# OLED_Shield_RV_2.net
KiCad netlist of a schematic drawn in EAGLE
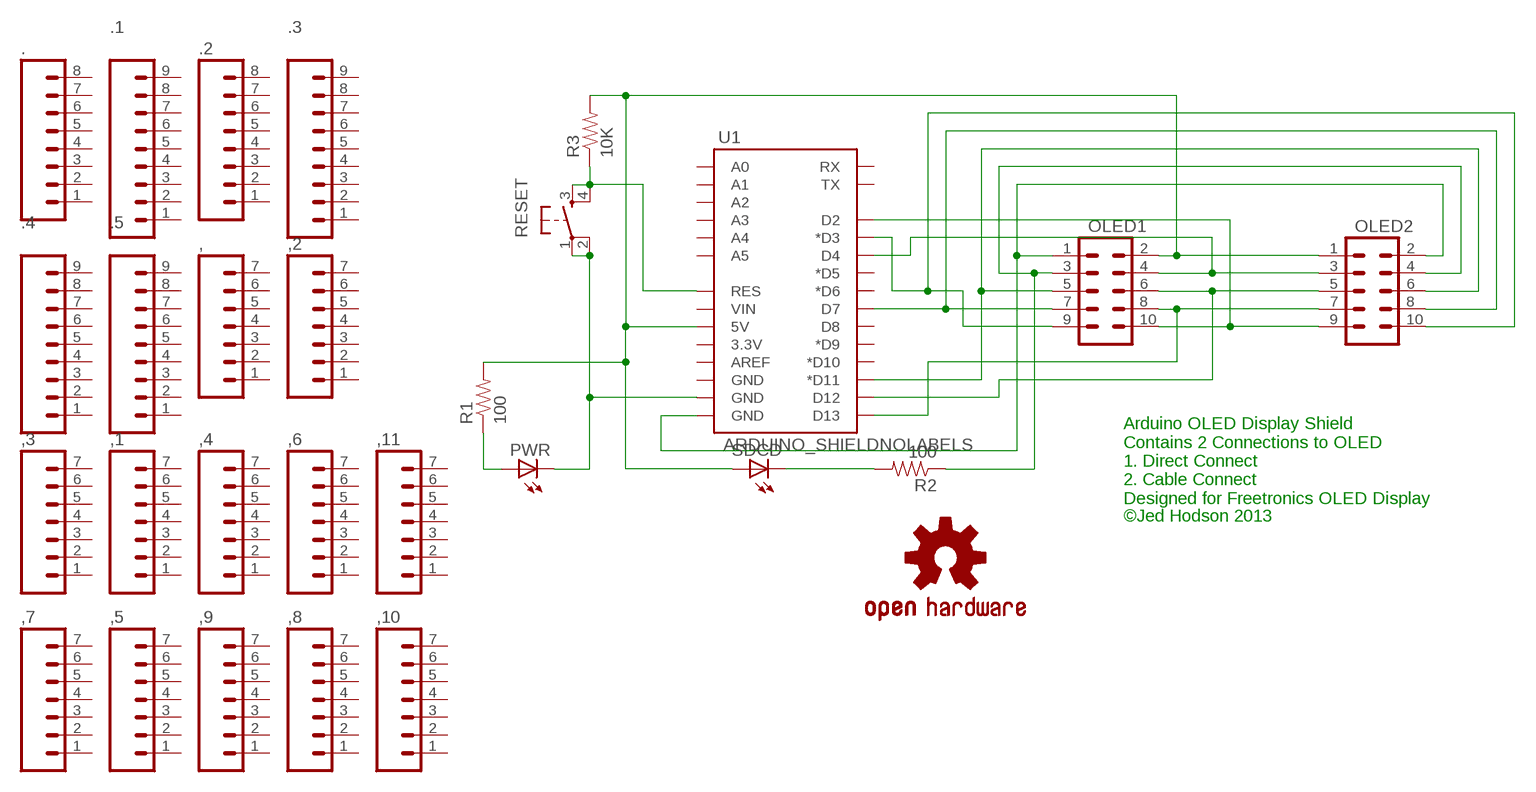
[diagram p0: schematic, sheet 1]

(export (version "E")
  (design (tool "Eeschema 10.0.6"))
  (components
    (comp (ref ",")
      (value "M07")
      (footprint "eagle-import:1X07")
      (libsource (lib "eagle-import") (part "M07"))
    )
    (comp (ref ",1")
      (value "M07")
      (footprint "eagle-import:1X07")
      (libsource (lib "eagle-import") (part "M07"))
    )
    (comp (ref ",2")
      (value "M07")
      (footprint "eagle-import:1X07")
      (libsource (lib "eagle-import") (part "M07"))
    )
    (comp (ref ",3")
      (value "M07")
      (footprint "eagle-import:1X07")
      (libsource (lib "eagle-import") (part "M07"))
    )
    (comp (ref ",4")
      (value "M07")
      (footprint "eagle-import:1X07")
      (libsource (lib "eagle-import") (part "M07"))
    )
    (comp (ref ",5")
      (value "M07")
      (footprint "eagle-import:1X07")
      (libsource (lib "eagle-import") (part "M07"))
    )
    (comp (ref ",6")
      (value "M07")
      (footprint "eagle-import:1X07")
      (libsource (lib "eagle-import") (part "M07"))
    )
    (comp (ref ",7")
      (value "M07")
      (footprint "eagle-import:1X07")
      (libsource (lib "eagle-import") (part "M07"))
    )
    (comp (ref ",8")
      (value "M07")
      (footprint "eagle-import:1X07")
      (libsource (lib "eagle-import") (part "M07"))
    )
    (comp (ref ",9")
      (value "M07")
      (footprint "eagle-import:1X07")
      (libsource (lib "eagle-import") (part "M07"))
    )
    (comp (ref ",10")
      (value "M07")
      (footprint "eagle-import:1X07")
      (libsource (lib "eagle-import") (part "M07"))
    )
    (comp (ref ",11")
      (value "M07")
      (footprint "eagle-import:1X07")
      (libsource (lib "eagle-import") (part "M07"))
    )
    (comp (ref ".")
      (value "M081X08")
      (footprint "eagle-import:1X08")
      (libsource (lib "eagle-import") (part "M081X08"))
    )
    (comp (ref ".1")
      (value "M09")
      (footprint "eagle-import:1X09")
      (libsource (lib "eagle-import") (part "M09"))
    )
    (comp (ref ".2")
      (value "M081X08")
      (footprint "eagle-import:1X08")
      (libsource (lib "eagle-import") (part "M081X08"))
    )
    (comp (ref ".3")
      (value "M09")
      (footprint "eagle-import:1X09")
      (libsource (lib "eagle-import") (part "M09"))
    )
    (comp (ref ".4")
      (value "M09")
      (footprint "eagle-import:1X09")
      (libsource (lib "eagle-import") (part "M09"))
    )
    (comp (ref ".5")
      (value "M09")
      (footprint "eagle-import:1X09")
      (libsource (lib "eagle-import") (part "M09"))
    )
    (comp (ref "LOGO1")
      (value "OSHW-LOGOL")
      (footprint "eagle-import:OSHW-LOGO-L")
      (libsource (lib "eagle-import") (part "OSHW-LOGOL"))
    )
    (comp (ref "OLED1")
      (value "M05X2PTH")
      (footprint "eagle-import:AVR_ICSP")
      (libsource (lib "eagle-import") (part "M05X2PTH"))
    )
    (comp (ref "OLED2")
      (value "M05X2PTH")
      (footprint "eagle-import:AVR_ICSP")
      (libsource (lib "eagle-import") (part "M05X2PTH"))
    )
    (comp (ref "PWR")
      (value "LED5MM")
      (footprint "eagle-import:LED5MM")
      (libsource (lib "eagle-import") (part "LED5MM"))
    )
    (comp (ref "R1")
      (value "100")
      (footprint "eagle-import:AXIAL-0.4")
      (libsource (lib "eagle-import") (part "RESISTORPTH-1/4W"))
    )
    (comp (ref "R2")
      (value "100")
      (footprint "eagle-import:AXIAL-0.4")
      (libsource (lib "eagle-import") (part "RESISTORPTH-1/4W"))
    )
    (comp (ref "R3")
      (value "10K")
      (footprint "eagle-import:AXIAL-0.4")
      (libsource (lib "eagle-import") (part "RESISTORPTH-1/4W"))
    )
    (comp (ref "RESET")
      (value "TAC_SWITCHPTH")
      (footprint "eagle-import:TACTILE-PTH")
      (libsource (lib "eagle-import") (part "TAC_SWITCHPTH"))
    )
    (comp (ref "SDCD")
      (value "LED5MM")
      (footprint "eagle-import:LED5MM")
      (libsource (lib "eagle-import") (part "LED5MM"))
    )
    (comp (ref "U1")
      (value "ARDUINO_SHIELDNOLABELS")
      (footprint "eagle-import:DUEMILANOVE_SHIELD_NOLABELS")
      (libsource (lib "eagle-import") (part "ARDUINO_SHIELDNOLABELS"))
    )
  )
  (nets
    (net (code "1") (name "Net-(OLED1-Pad1)") (class "Default")
      (node (ref "OLED1") (pin "1") (pinfunction "1_1") (pintype "passive"))
      (node (ref "OLED2") (pin "2") (pinfunction "2_2") (pintype "passive"))
      (node (ref "U1") (pin "GND@0") (pinfunction "GND_GND@0") (pintype "bidirectional"))
    )
    (net (code "2") (name "Net-(OLED1-Pad4)") (class "Default")
      (node (ref "OLED1") (pin "4") (pinfunction "4_4") (pintype "passive"))
      (node (ref "OLED2") (pin "3") (pinfunction "3_3") (pintype "passive"))
      (node (ref "U1") (pin "D4") (pinfunction "D4_D4") (pintype "bidirectional"))
    )
    (net (code "3") (name "Net-(OLED1-Pad6)") (class "Default")
      (node (ref "OLED1") (pin "6") (pinfunction "6_6") (pintype "passive"))
      (node (ref "OLED2") (pin "5") (pinfunction "5_5") (pintype "passive"))
      (node (ref "U1") (pin "D12") (pinfunction "D12_D12") (pintype "bidirectional"))
    )
    (net (code "4") (name "Net-(OLED1-Pad7)") (class "Default")
      (node (ref "OLED1") (pin "7") (pinfunction "7_7") (pintype "passive"))
      (node (ref "OLED2") (pin "8") (pinfunction "8_8") (pintype "passive"))
      (node (ref "U1") (pin "D7") (pinfunction "D7_D7") (pintype "bidirectional"))
    )
    (net (code "5") (name "Net-(OLED1-Pad8)") (class "Default")
      (node (ref "OLED1") (pin "8") (pinfunction "8_8") (pintype "passive"))
      (node (ref "OLED2") (pin "7") (pinfunction "7_7") (pintype "passive"))
      (node (ref "U1") (pin "D13") (pinfunction "D13_D13") (pintype "bidirectional"))
    )
    (net (code "6") (name "Net-(OLED1-Pad10)") (class "Default")
      (node (ref "OLED1") (pin "10") (pinfunction "10_10") (pintype "passive"))
      (node (ref "OLED2") (pin "9") (pinfunction "9_9") (pintype "passive"))
      (node (ref "U1") (pin "D2") (pinfunction "D2_D2") (pintype "bidirectional"))
    )
    (net (code "7") (name "Net-(PWR-C)") (class "Default")
      (node (ref "PWR") (pin "K") (pinfunction "C_K") (pintype "passive"))
      (node (ref "RESET") (pin "1") (pinfunction "1_1") (pintype "passive"))
      (node (ref "RESET") (pin "2") (pinfunction "2_2") (pintype "passive"))
      (node (ref "U1") (pin "GND@1") (pinfunction "GND_GND@1") (pintype "bidirectional"))
    )
    (net (code "8") (name "Net-(R1-1)") (class "Default")
      (node (ref "PWR") (pin "A") (pinfunction "A_A") (pintype "passive"))
      (node (ref "R1") (pin "P$1") (pinfunction "1_P$1") (pintype "passive"))
    )
    (net (code "9") (name "Net-(R1-2)") (class "Default")
      (node (ref "OLED1") (pin "2") (pinfunction "2_2") (pintype "passive"))
      (node (ref "OLED2") (pin "1") (pinfunction "1_1") (pintype "passive"))
      (node (ref "R1") (pin "P$2") (pinfunction "2_P$2") (pintype "passive"))
      (node (ref "R3") (pin "P$2") (pinfunction "2_P$2") (pintype "passive"))
      (node (ref "SDCD") (pin "A") (pinfunction "A_A") (pintype "passive"))
      (node (ref "U1") (pin "5V") (pinfunction "5V_5V") (pintype "bidirectional"))
    )
    (net (code "10") (name "Net-(R2-1)") (class "Default")
      (node (ref "OLED1") (pin "3") (pinfunction "3_3") (pintype "passive"))
      (node (ref "OLED2") (pin "4") (pinfunction "4_4") (pintype "passive"))
      (node (ref "R2") (pin "P$1") (pinfunction "1_P$1") (pintype "passive"))
    )
    (net (code "11") (name "Net-(R2-2)") (class "Default")
      (node (ref "R2") (pin "P$2") (pinfunction "2_P$2") (pintype "passive"))
      (node (ref "SDCD") (pin "K") (pinfunction "C_K") (pintype "passive"))
    )
    (net (code "12") (name "Net-(R3-1)") (class "Default")
      (node (ref "R3") (pin "P$1") (pinfunction "1_P$1") (pintype "passive"))
      (node (ref "RESET") (pin "3") (pinfunction "3_3") (pintype "passive"))
      (node (ref "RESET") (pin "4") (pinfunction "4_4") (pintype "passive"))
      (node (ref "U1") (pin "RES") (pinfunction "RES_RES") (pintype "bidirectional"))
    )
    (net (code "13") (name "Net-(U1-*D3)") (class "Default")
      (node (ref "OLED1") (pin "9") (pinfunction "9_9") (pintype "passive"))
      (node (ref "OLED2") (pin "10") (pinfunction "10_10") (pintype "passive"))
      (node (ref "U1") (pin "D3") (pinfunction "*D3_D3") (pintype "bidirectional"))
    )
    (net (code "14") (name "Net-(U1-*D11)") (class "Default")
      (node (ref "OLED1") (pin "5") (pinfunction "5_5") (pintype "passive"))
      (node (ref "OLED2") (pin "6") (pinfunction "6_6") (pintype "passive"))
      (node (ref "U1") (pin "D11") (pinfunction "*D11_D11") (pintype "bidirectional"))
    )
    (net (code "15") (name "unconnected-(,-Pad1)") (class "Default")
      (node (ref ",") (pin "1") (pinfunction "1_1") (pintype "passive"))
    )
    (net (code "16") (name "unconnected-(,-Pad2)") (class "Default")
      (node (ref ",") (pin "2") (pinfunction "2_2") (pintype "passive"))
    )
    (net (code "17") (name "unconnected-(,-Pad3)") (class "Default")
      (node (ref ",") (pin "3") (pinfunction "3_3") (pintype "passive"))
    )
    (net (code "18") (name "unconnected-(,-Pad4)") (class "Default")
      (node (ref ",") (pin "4") (pinfunction "4_4") (pintype "passive"))
    )
    (net (code "19") (name "unconnected-(,-Pad5)") (class "Default")
      (node (ref ",") (pin "5") (pinfunction "5_5") (pintype "passive"))
    )
    (net (code "20") (name "unconnected-(,-Pad6)") (class "Default")
      (node (ref ",") (pin "6") (pinfunction "6_6") (pintype "passive"))
    )
    (net (code "21") (name "unconnected-(,-Pad7)") (class "Default")
      (node (ref ",") (pin "7") (pinfunction "7_7") (pintype "passive"))
    )
    (net (code "22") (name "unconnected-(,1-Pad1)") (class "Default")
      (node (ref ",1") (pin "1") (pinfunction "1_1") (pintype "passive"))
    )
    (net (code "23") (name "unconnected-(,1-Pad2)") (class "Default")
      (node (ref ",1") (pin "2") (pinfunction "2_2") (pintype "passive"))
    )
    (net (code "24") (name "unconnected-(,1-Pad3)") (class "Default")
      (node (ref ",1") (pin "3") (pinfunction "3_3") (pintype "passive"))
    )
    (net (code "25") (name "unconnected-(,1-Pad4)") (class "Default")
      (node (ref ",1") (pin "4") (pinfunction "4_4") (pintype "passive"))
    )
    (net (code "26") (name "unconnected-(,1-Pad5)") (class "Default")
      (node (ref ",1") (pin "5") (pinfunction "5_5") (pintype "passive"))
    )
    (net (code "27") (name "unconnected-(,1-Pad6)") (class "Default")
      (node (ref ",1") (pin "6") (pinfunction "6_6") (pintype "passive"))
    )
    (net (code "28") (name "unconnected-(,1-Pad7)") (class "Default")
      (node (ref ",1") (pin "7") (pinfunction "7_7") (pintype "passive"))
    )
    (net (code "29") (name "unconnected-(,2-Pad1)") (class "Default")
      (node (ref ",2") (pin "1") (pinfunction "1_1") (pintype "passive"))
    )
    (net (code "30") (name "unconnected-(,2-Pad2)") (class "Default")
      (node (ref ",2") (pin "2") (pinfunction "2_2") (pintype "passive"))
    )
    (net (code "31") (name "unconnected-(,2-Pad3)") (class "Default")
      (node (ref ",2") (pin "3") (pinfunction "3_3") (pintype "passive"))
    )
    (net (code "32") (name "unconnected-(,2-Pad4)") (class "Default")
      (node (ref ",2") (pin "4") (pinfunction "4_4") (pintype "passive"))
    )
    (net (code "33") (name "unconnected-(,2-Pad5)") (class "Default")
      (node (ref ",2") (pin "5") (pinfunction "5_5") (pintype "passive"))
    )
    (net (code "34") (name "unconnected-(,2-Pad6)") (class "Default")
      (node (ref ",2") (pin "6") (pinfunction "6_6") (pintype "passive"))
    )
    (net (code "35") (name "unconnected-(,2-Pad7)") (class "Default")
      (node (ref ",2") (pin "7") (pinfunction "7_7") (pintype "passive"))
    )
    (net (code "36") (name "unconnected-(,3-Pad1)") (class "Default")
      (node (ref ",3") (pin "1") (pinfunction "1_1") (pintype "passive"))
    )
    (net (code "37") (name "unconnected-(,3-Pad2)") (class "Default")
      (node (ref ",3") (pin "2") (pinfunction "2_2") (pintype "passive"))
    )
    (net (code "38") (name "unconnected-(,3-Pad3)") (class "Default")
      (node (ref ",3") (pin "3") (pinfunction "3_3") (pintype "passive"))
    )
    (net (code "39") (name "unconnected-(,3-Pad4)") (class "Default")
      (node (ref ",3") (pin "4") (pinfunction "4_4") (pintype "passive"))
    )
    (net (code "40") (name "unconnected-(,3-Pad5)") (class "Default")
      (node (ref ",3") (pin "5") (pinfunction "5_5") (pintype "passive"))
    )
    (net (code "41") (name "unconnected-(,3-Pad6)") (class "Default")
      (node (ref ",3") (pin "6") (pinfunction "6_6") (pintype "passive"))
    )
    (net (code "42") (name "unconnected-(,3-Pad7)") (class "Default")
      (node (ref ",3") (pin "7") (pinfunction "7_7") (pintype "passive"))
    )
    (net (code "43") (name "unconnected-(,4-Pad1)") (class "Default")
      (node (ref ",4") (pin "1") (pinfunction "1_1") (pintype "passive"))
    )
    (net (code "44") (name "unconnected-(,4-Pad2)") (class "Default")
      (node (ref ",4") (pin "2") (pinfunction "2_2") (pintype "passive"))
    )
    (net (code "45") (name "unconnected-(,4-Pad3)") (class "Default")
      (node (ref ",4") (pin "3") (pinfunction "3_3") (pintype "passive"))
    )
    (net (code "46") (name "unconnected-(,4-Pad4)") (class "Default")
      (node (ref ",4") (pin "4") (pinfunction "4_4") (pintype "passive"))
    )
    (net (code "47") (name "unconnected-(,4-Pad5)") (class "Default")
      (node (ref ",4") (pin "5") (pinfunction "5_5") (pintype "passive"))
    )
    (net (code "48") (name "unconnected-(,4-Pad6)") (class "Default")
      (node (ref ",4") (pin "6") (pinfunction "6_6") (pintype "passive"))
    )
    (net (code "49") (name "unconnected-(,4-Pad7)") (class "Default")
      (node (ref ",4") (pin "7") (pinfunction "7_7") (pintype "passive"))
    )
    (net (code "50") (name "unconnected-(,5-Pad1)") (class "Default")
      (node (ref ",5") (pin "1") (pinfunction "1_1") (pintype "passive"))
    )
    (net (code "51") (name "unconnected-(,5-Pad2)") (class "Default")
      (node (ref ",5") (pin "2") (pinfunction "2_2") (pintype "passive"))
    )
    (net (code "52") (name "unconnected-(,5-Pad3)") (class "Default")
      (node (ref ",5") (pin "3") (pinfunction "3_3") (pintype "passive"))
    )
    (net (code "53") (name "unconnected-(,5-Pad4)") (class "Default")
      (node (ref ",5") (pin "4") (pinfunction "4_4") (pintype "passive"))
    )
    (net (code "54") (name "unconnected-(,5-Pad5)") (class "Default")
      (node (ref ",5") (pin "5") (pinfunction "5_5") (pintype "passive"))
    )
    (net (code "55") (name "unconnected-(,5-Pad6)") (class "Default")
      (node (ref ",5") (pin "6") (pinfunction "6_6") (pintype "passive"))
    )
    (net (code "56") (name "unconnected-(,5-Pad7)") (class "Default")
      (node (ref ",5") (pin "7") (pinfunction "7_7") (pintype "passive"))
    )
    (net (code "57") (name "unconnected-(,6-Pad1)") (class "Default")
      (node (ref ",6") (pin "1") (pinfunction "1_1") (pintype "passive"))
    )
    (net (code "58") (name "unconnected-(,6-Pad2)") (class "Default")
      (node (ref ",6") (pin "2") (pinfunction "2_2") (pintype "passive"))
    )
    (net (code "59") (name "unconnected-(,6-Pad3)") (class "Default")
      (node (ref ",6") (pin "3") (pinfunction "3_3") (pintype "passive"))
    )
    (net (code "60") (name "unconnected-(,6-Pad4)") (class "Default")
      (node (ref ",6") (pin "4") (pinfunction "4_4") (pintype "passive"))
    )
    (net (code "61") (name "unconnected-(,6-Pad5)") (class "Default")
      (node (ref ",6") (pin "5") (pinfunction "5_5") (pintype "passive"))
    )
    (net (code "62") (name "unconnected-(,6-Pad6)") (class "Default")
      (node (ref ",6") (pin "6") (pinfunction "6_6") (pintype "passive"))
    )
    (net (code "63") (name "unconnected-(,6-Pad7)") (class "Default")
      (node (ref ",6") (pin "7") (pinfunction "7_7") (pintype "passive"))
    )
    (net (code "64") (name "unconnected-(,7-Pad1)") (class "Default")
      (node (ref ",7") (pin "1") (pinfunction "1_1") (pintype "passive"))
    )
    (net (code "65") (name "unconnected-(,7-Pad2)") (class "Default")
      (node (ref ",7") (pin "2") (pinfunction "2_2") (pintype "passive"))
    )
    (net (code "66") (name "unconnected-(,7-Pad3)") (class "Default")
      (node (ref ",7") (pin "3") (pinfunction "3_3") (pintype "passive"))
    )
    (net (code "67") (name "unconnected-(,7-Pad4)") (class "Default")
      (node (ref ",7") (pin "4") (pinfunction "4_4") (pintype "passive"))
    )
    (net (code "68") (name "unconnected-(,7-Pad5)") (class "Default")
      (node (ref ",7") (pin "5") (pinfunction "5_5") (pintype "passive"))
    )
    (net (code "69") (name "unconnected-(,7-Pad6)") (class "Default")
      (node (ref ",7") (pin "6") (pinfunction "6_6") (pintype "passive"))
    )
    (net (code "70") (name "unconnected-(,7-Pad7)") (class "Default")
      (node (ref ",7") (pin "7") (pinfunction "7_7") (pintype "passive"))
    )
    (net (code "71") (name "unconnected-(,8-Pad1)") (class "Default")
      (node (ref ",8") (pin "1") (pinfunction "1_1") (pintype "passive"))
    )
    (net (code "72") (name "unconnected-(,8-Pad2)") (class "Default")
      (node (ref ",8") (pin "2") (pinfunction "2_2") (pintype "passive"))
    )
    (net (code "73") (name "unconnected-(,8-Pad3)") (class "Default")
      (node (ref ",8") (pin "3") (pinfunction "3_3") (pintype "passive"))
    )
    (net (code "74") (name "unconnected-(,8-Pad4)") (class "Default")
      (node (ref ",8") (pin "4") (pinfunction "4_4") (pintype "passive"))
    )
    (net (code "75") (name "unconnected-(,8-Pad5)") (class "Default")
      (node (ref ",8") (pin "5") (pinfunction "5_5") (pintype "passive"))
    )
    (net (code "76") (name "unconnected-(,8-Pad6)") (class "Default")
      (node (ref ",8") (pin "6") (pinfunction "6_6") (pintype "passive"))
    )
    (net (code "77") (name "unconnected-(,8-Pad7)") (class "Default")
      (node (ref ",8") (pin "7") (pinfunction "7_7") (pintype "passive"))
    )
    (net (code "78") (name "unconnected-(,9-Pad1)") (class "Default")
      (node (ref ",9") (pin "1") (pinfunction "1_1") (pintype "passive"))
    )
    (net (code "79") (name "unconnected-(,9-Pad2)") (class "Default")
      (node (ref ",9") (pin "2") (pinfunction "2_2") (pintype "passive"))
    )
    (net (code "80") (name "unconnected-(,9-Pad3)") (class "Default")
      (node (ref ",9") (pin "3") (pinfunction "3_3") (pintype "passive"))
    )
    (net (code "81") (name "unconnected-(,9-Pad4)") (class "Default")
      (node (ref ",9") (pin "4") (pinfunction "4_4") (pintype "passive"))
    )
    (net (code "82") (name "unconnected-(,9-Pad5)") (class "Default")
      (node (ref ",9") (pin "5") (pinfunction "5_5") (pintype "passive"))
    )
    (net (code "83") (name "unconnected-(,9-Pad6)") (class "Default")
      (node (ref ",9") (pin "6") (pinfunction "6_6") (pintype "passive"))
    )
    (net (code "84") (name "unconnected-(,9-Pad7)") (class "Default")
      (node (ref ",9") (pin "7") (pinfunction "7_7") (pintype "passive"))
    )
    (net (code "85") (name "unconnected-(,10-Pad1)") (class "Default")
      (node (ref ",10") (pin "1") (pinfunction "1_1") (pintype "passive"))
    )
    (net (code "86") (name "unconnected-(,10-Pad2)") (class "Default")
      (node (ref ",10") (pin "2") (pinfunction "2_2") (pintype "passive"))
    )
    (net (code "87") (name "unconnected-(,10-Pad3)") (class "Default")
      (node (ref ",10") (pin "3") (pinfunction "3_3") (pintype "passive"))
    )
    (net (code "88") (name "unconnected-(,10-Pad4)") (class "Default")
      (node (ref ",10") (pin "4") (pinfunction "4_4") (pintype "passive"))
    )
    (net (code "89") (name "unconnected-(,10-Pad5)") (class "Default")
      (node (ref ",10") (pin "5") (pinfunction "5_5") (pintype "passive"))
    )
    (net (code "90") (name "unconnected-(,10-Pad6)") (class "Default")
      (node (ref ",10") (pin "6") (pinfunction "6_6") (pintype "passive"))
    )
    (net (code "91") (name "unconnected-(,10-Pad7)") (class "Default")
      (node (ref ",10") (pin "7") (pinfunction "7_7") (pintype "passive"))
    )
    (net (code "92") (name "unconnected-(,11-Pad1)") (class "Default")
      (node (ref ",11") (pin "1") (pinfunction "1_1") (pintype "passive"))
    )
    (net (code "93") (name "unconnected-(,11-Pad2)") (class "Default")
      (node (ref ",11") (pin "2") (pinfunction "2_2") (pintype "passive"))
    )
    (net (code "94") (name "unconnected-(,11-Pad3)") (class "Default")
      (node (ref ",11") (pin "3") (pinfunction "3_3") (pintype "passive"))
    )
    (net (code "95") (name "unconnected-(,11-Pad4)") (class "Default")
      (node (ref ",11") (pin "4") (pinfunction "4_4") (pintype "passive"))
    )
    (net (code "96") (name "unconnected-(,11-Pad5)") (class "Default")
      (node (ref ",11") (pin "5") (pinfunction "5_5") (pintype "passive"))
    )
    (net (code "97") (name "unconnected-(,11-Pad6)") (class "Default")
      (node (ref ",11") (pin "6") (pinfunction "6_6") (pintype "passive"))
    )
    (net (code "98") (name "unconnected-(,11-Pad7)") (class "Default")
      (node (ref ",11") (pin "7") (pinfunction "7_7") (pintype "passive"))
    )
    (net (code "99") (name "unconnected-(.-Pad1)") (class "Default")
      (node (ref ".") (pin "1") (pinfunction "1_1") (pintype "passive"))
    )
    (net (code "100") (name "unconnected-(.-Pad2)") (class "Default")
      (node (ref ".") (pin "2") (pinfunction "2_2") (pintype "passive"))
    )
    (net (code "101") (name "unconnected-(.-Pad3)") (class "Default")
      (node (ref ".") (pin "3") (pinfunction "3_3") (pintype "passive"))
    )
    (net (code "102") (name "unconnected-(.-Pad4)") (class "Default")
      (node (ref ".") (pin "4") (pinfunction "4_4") (pintype "passive"))
    )
    (net (code "103") (name "unconnected-(.-Pad5)") (class "Default")
      (node (ref ".") (pin "5") (pinfunction "5_5") (pintype "passive"))
    )
    (net (code "104") (name "unconnected-(.-Pad6)") (class "Default")
      (node (ref ".") (pin "6") (pinfunction "6_6") (pintype "passive"))
    )
    (net (code "105") (name "unconnected-(.-Pad7)") (class "Default")
      (node (ref ".") (pin "7") (pinfunction "7_7") (pintype "passive"))
    )
    (net (code "106") (name "unconnected-(.-Pad8)") (class "Default")
      (node (ref ".") (pin "8") (pinfunction "8_8") (pintype "passive"))
    )
    (net (code "107") (name "unconnected-(.1-Pad1)") (class "Default")
      (node (ref ".1") (pin "1") (pinfunction "1_1") (pintype "passive"))
    )
    (net (code "108") (name "unconnected-(.1-Pad2)") (class "Default")
      (node (ref ".1") (pin "2") (pinfunction "2_2") (pintype "passive"))
    )
    (net (code "109") (name "unconnected-(.1-Pad3)") (class "Default")
      (node (ref ".1") (pin "3") (pinfunction "3_3") (pintype "passive"))
    )
    (net (code "110") (name "unconnected-(.1-Pad4)") (class "Default")
      (node (ref ".1") (pin "4") (pinfunction "4_4") (pintype "passive"))
    )
    (net (code "111") (name "unconnected-(.1-Pad5)") (class "Default")
      (node (ref ".1") (pin "5") (pinfunction "5_5") (pintype "passive"))
    )
    (net (code "112") (name "unconnected-(.1-Pad6)") (class "Default")
      (node (ref ".1") (pin "6") (pinfunction "6_6") (pintype "passive"))
    )
    (net (code "113") (name "unconnected-(.1-Pad7)") (class "Default")
      (node (ref ".1") (pin "7") (pinfunction "7_7") (pintype "passive"))
    )
    (net (code "114") (name "unconnected-(.1-Pad8)") (class "Default")
      (node (ref ".1") (pin "8") (pinfunction "8_8") (pintype "passive"))
    )
    (net (code "115") (name "unconnected-(.1-Pad9)") (class "Default")
      (node (ref ".1") (pin "9") (pinfunction "9_9") (pintype "passive"))
    )
    (net (code "116") (name "unconnected-(.2-Pad1)") (class "Default")
      (node (ref ".2") (pin "1") (pinfunction "1_1") (pintype "passive"))
    )
    (net (code "117") (name "unconnected-(.2-Pad2)") (class "Default")
      (node (ref ".2") (pin "2") (pinfunction "2_2") (pintype "passive"))
    )
    (net (code "118") (name "unconnected-(.2-Pad3)") (class "Default")
      (node (ref ".2") (pin "3") (pinfunction "3_3") (pintype "passive"))
    )
    (net (code "119") (name "unconnected-(.2-Pad4)") (class "Default")
      (node (ref ".2") (pin "4") (pinfunction "4_4") (pintype "passive"))
    )
    (net (code "120") (name "unconnected-(.2-Pad5)") (class "Default")
      (node (ref ".2") (pin "5") (pinfunction "5_5") (pintype "passive"))
    )
    (net (code "121") (name "unconnected-(.2-Pad6)") (class "Default")
      (node (ref ".2") (pin "6") (pinfunction "6_6") (pintype "passive"))
    )
    (net (code "122") (name "unconnected-(.2-Pad7)") (class "Default")
      (node (ref ".2") (pin "7") (pinfunction "7_7") (pintype "passive"))
    )
    (net (code "123") (name "unconnected-(.2-Pad8)") (class "Default")
      (node (ref ".2") (pin "8") (pinfunction "8_8") (pintype "passive"))
    )
    (net (code "124") (name "unconnected-(.3-Pad1)") (class "Default")
      (node (ref ".3") (pin "1") (pinfunction "1_1") (pintype "passive"))
    )
    (net (code "125") (name "unconnected-(.3-Pad2)") (class "Default")
      (node (ref ".3") (pin "2") (pinfunction "2_2") (pintype "passive"))
    )
    (net (code "126") (name "unconnected-(.3-Pad3)") (class "Default")
      (node (ref ".3") (pin "3") (pinfunction "3_3") (pintype "passive"))
    )
    (net (code "127") (name "unconnected-(.3-Pad4)") (class "Default")
      (node (ref ".3") (pin "4") (pinfunction "4_4") (pintype "passive"))
    )
    (net (code "128") (name "unconnected-(.3-Pad5)") (class "Default")
      (node (ref ".3") (pin "5") (pinfunction "5_5") (pintype "passive"))
    )
    (net (code "129") (name "unconnected-(.3-Pad6)") (class "Default")
      (node (ref ".3") (pin "6") (pinfunction "6_6") (pintype "passive"))
    )
    (net (code "130") (name "unconnected-(.3-Pad7)") (class "Default")
      (node (ref ".3") (pin "7") (pinfunction "7_7") (pintype "passive"))
    )
    (net (code "131") (name "unconnected-(.3-Pad8)") (class "Default")
      (node (ref ".3") (pin "8") (pinfunction "8_8") (pintype "passive"))
    )
    (net (code "132") (name "unconnected-(.3-Pad9)") (class "Default")
      (node (ref ".3") (pin "9") (pinfunction "9_9") (pintype "passive"))
    )
    (net (code "133") (name "unconnected-(.4-Pad1)") (class "Default")
      (node (ref ".4") (pin "1") (pinfunction "1_1") (pintype "passive"))
    )
    (net (code "134") (name "unconnected-(.4-Pad2)") (class "Default")
      (node (ref ".4") (pin "2") (pinfunction "2_2") (pintype "passive"))
    )
    (net (code "135") (name "unconnected-(.4-Pad3)") (class "Default")
      (node (ref ".4") (pin "3") (pinfunction "3_3") (pintype "passive"))
    )
    (net (code "136") (name "unconnected-(.4-Pad4)") (class "Default")
      (node (ref ".4") (pin "4") (pinfunction "4_4") (pintype "passive"))
    )
    (net (code "137") (name "unconnected-(.4-Pad5)") (class "Default")
      (node (ref ".4") (pin "5") (pinfunction "5_5") (pintype "passive"))
    )
    (net (code "138") (name "unconnected-(.4-Pad6)") (class "Default")
      (node (ref ".4") (pin "6") (pinfunction "6_6") (pintype "passive"))
    )
    (net (code "139") (name "unconnected-(.4-Pad7)") (class "Default")
      (node (ref ".4") (pin "7") (pinfunction "7_7") (pintype "passive"))
    )
    (net (code "140") (name "unconnected-(.4-Pad8)") (class "Default")
      (node (ref ".4") (pin "8") (pinfunction "8_8") (pintype "passive"))
    )
    (net (code "141") (name "unconnected-(.4-Pad9)") (class "Default")
      (node (ref ".4") (pin "9") (pinfunction "9_9") (pintype "passive"))
    )
    (net (code "142") (name "unconnected-(.5-Pad1)") (class "Default")
      (node (ref ".5") (pin "1") (pinfunction "1_1") (pintype "passive"))
    )
    (net (code "143") (name "unconnected-(.5-Pad2)") (class "Default")
      (node (ref ".5") (pin "2") (pinfunction "2_2") (pintype "passive"))
    )
    (net (code "144") (name "unconnected-(.5-Pad3)") (class "Default")
      (node (ref ".5") (pin "3") (pinfunction "3_3") (pintype "passive"))
    )
    (net (code "145") (name "unconnected-(.5-Pad4)") (class "Default")
      (node (ref ".5") (pin "4") (pinfunction "4_4") (pintype "passive"))
    )
    (net (code "146") (name "unconnected-(.5-Pad5)") (class "Default")
      (node (ref ".5") (pin "5") (pinfunction "5_5") (pintype "passive"))
    )
    (net (code "147") (name "unconnected-(.5-Pad6)") (class "Default")
      (node (ref ".5") (pin "6") (pinfunction "6_6") (pintype "passive"))
    )
    (net (code "148") (name "unconnected-(.5-Pad7)") (class "Default")
      (node (ref ".5") (pin "7") (pinfunction "7_7") (pintype "passive"))
    )
    (net (code "149") (name "unconnected-(.5-Pad8)") (class "Default")
      (node (ref ".5") (pin "8") (pinfunction "8_8") (pintype "passive"))
    )
    (net (code "150") (name "unconnected-(.5-Pad9)") (class "Default")
      (node (ref ".5") (pin "9") (pinfunction "9_9") (pintype "passive"))
    )
    (net (code "151") (name "unconnected-(U1-*D5-PadD5)") (class "Default")
      (node (ref "U1") (pin "D5") (pinfunction "*D5_D5") (pintype "bidirectional"))
    )
    (net (code "152") (name "unconnected-(U1-*D6-PadD6)") (class "Default")
      (node (ref "U1") (pin "D6") (pinfunction "*D6_D6") (pintype "bidirectional"))
    )
    (net (code "153") (name "unconnected-(U1-*D9-PadD9)") (class "Default")
      (node (ref "U1") (pin "D9") (pinfunction "*D9_D9") (pintype "bidirectional"))
    )
    (net (code "154") (name "unconnected-(U1-*D10-PadD10)") (class "Default")
      (node (ref "U1") (pin "D10") (pinfunction "*D10_D10") (pintype "bidirectional"))
    )
    (net (code "155") (name "unconnected-(U1-GND-PadGND@2)") (class "Default")
      (node (ref "U1") (pin "GND@2") (pinfunction "GND_GND@2") (pintype "bidirectional"))
    )
    (net (code "156") (name "unconnected-(U1-Pad3.3V)") (class "Default")
      (node (ref "U1") (pin "3.3V") (pinfunction "3.3V_3.3V") (pintype "bidirectional"))
    )
    (net (code "157") (name "unconnected-(U1-PadA0)") (class "Default")
      (node (ref "U1") (pin "A0") (pinfunction "A0_A0") (pintype "bidirectional"))
    )
    (net (code "158") (name "unconnected-(U1-PadA1)") (class "Default")
      (node (ref "U1") (pin "A1") (pinfunction "A1_A1") (pintype "bidirectional"))
    )
    (net (code "159") (name "unconnected-(U1-PadA2)") (class "Default")
      (node (ref "U1") (pin "A2") (pinfunction "A2_A2") (pintype "bidirectional"))
    )
    (net (code "160") (name "unconnected-(U1-PadA3)") (class "Default")
      (node (ref "U1") (pin "A3") (pinfunction "A3_A3") (pintype "bidirectional"))
    )
    (net (code "161") (name "unconnected-(U1-PadA4)") (class "Default")
      (node (ref "U1") (pin "A4") (pinfunction "A4_A4") (pintype "bidirectional"))
    )
    (net (code "162") (name "unconnected-(U1-PadA5)") (class "Default")
      (node (ref "U1") (pin "A5") (pinfunction "A5_A5") (pintype "bidirectional"))
    )
    (net (code "163") (name "unconnected-(U1-PadAREF)") (class "Default")
      (node (ref "U1") (pin "AREF") (pinfunction "AREF_AREF") (pintype "bidirectional"))
    )
    (net (code "164") (name "unconnected-(U1-PadD8)") (class "Default")
      (node (ref "U1") (pin "D8") (pinfunction "D8_D8") (pintype "bidirectional"))
    )
    (net (code "165") (name "unconnected-(U1-PadRX)") (class "Default")
      (node (ref "U1") (pin "RX") (pinfunction "RX_RX") (pintype "bidirectional"))
    )
    (net (code "166") (name "unconnected-(U1-PadTX)") (class "Default")
      (node (ref "U1") (pin "TX") (pinfunction "TX_TX") (pintype "bidirectional"))
    )
    (net (code "167") (name "unconnected-(U1-PadVIN)") (class "Default")
      (node (ref "U1") (pin "VIN") (pinfunction "VIN_VIN") (pintype "bidirectional"))
    )
  )
)
